# Upstream.net
KiCad netlist of a schematic drawn in Altium Designer
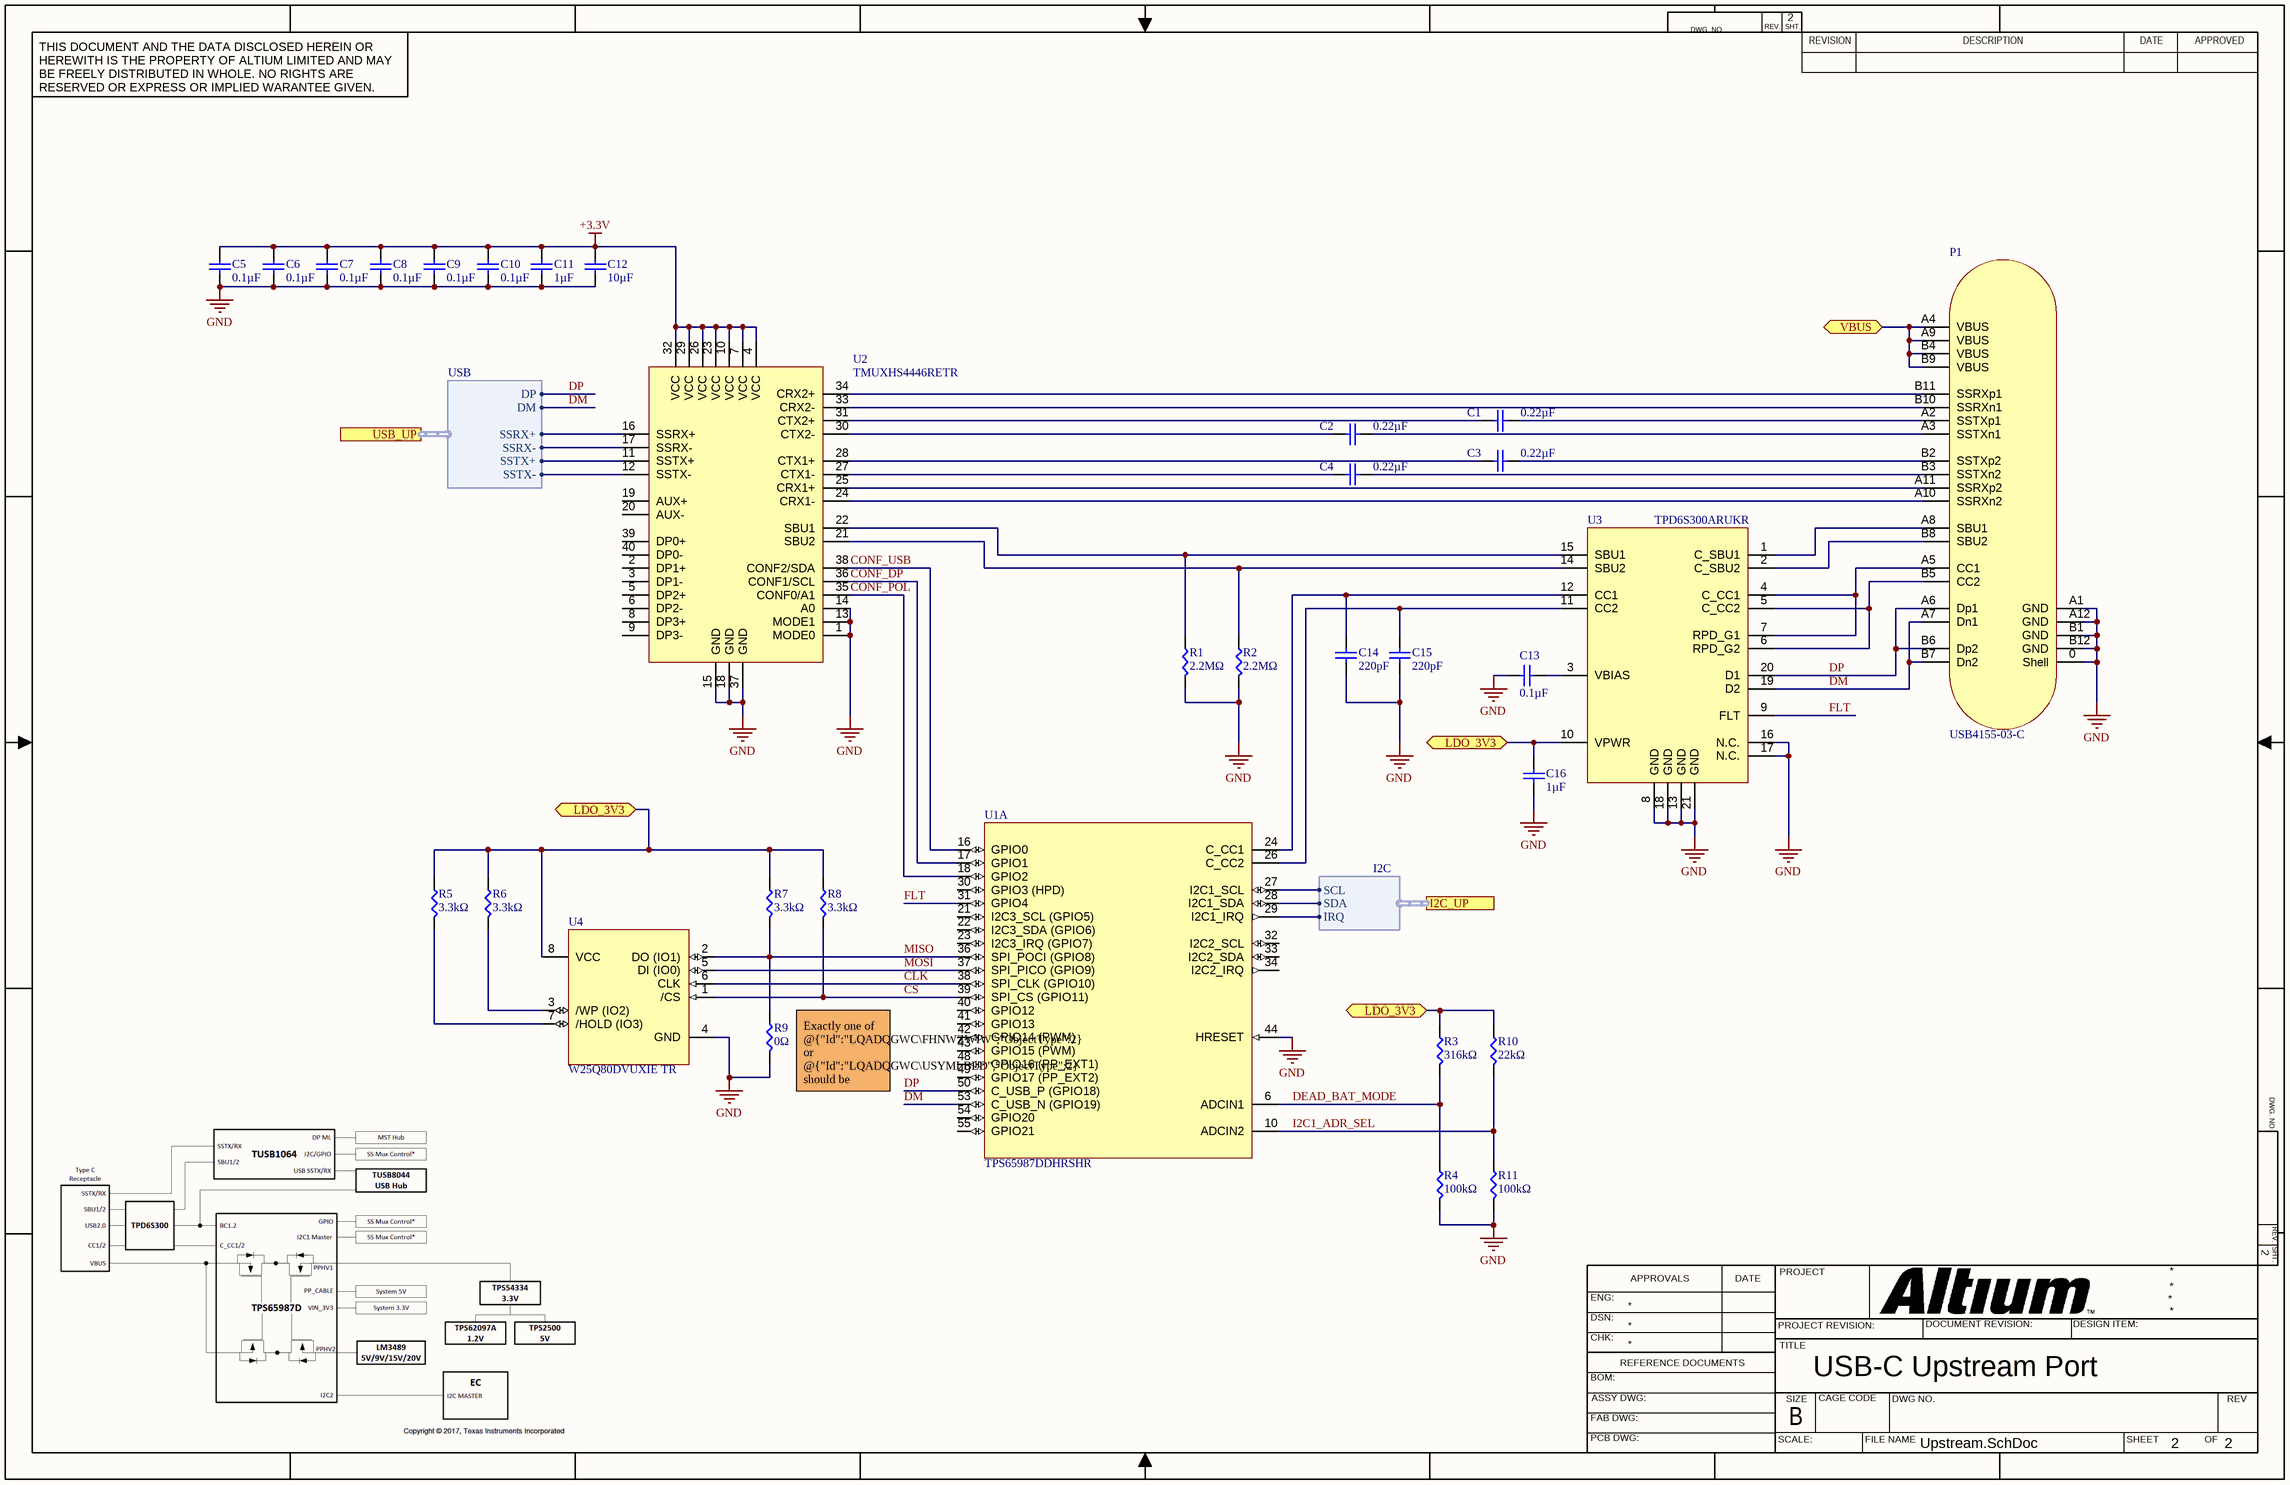
[diagram p0: Upstream.SchDoc]

(export (version "E")
  (design (tool "Eeschema 10.0.6"))
  (components
    (comp (ref "C1")
      (value "0.22µF")
      (footprint "CAP0402")
      (description "0.22 µF ±10% 50V Ceramic Capacitor X5R 0402 (1005 Metric)")
      (fields (field (name "VOLTAGE") "50V") (field (name "Comment") "UMK105BJ224KV-F"))
      (libsource (lib "Schlib1") (part "UMK105BJ224KV-F"))
    )
    (comp (ref "C2")
      (value "0.22µF")
      (footprint "CAP0402")
      (description "0.22 µF ±10% 50V Ceramic Capacitor X5R 0402 (1005 Metric)")
      (fields (field (name "VOLTAGE") "50V") (field (name "Comment") "UMK105BJ224KV-F"))
      (libsource (lib "Schlib1") (part "UMK105BJ224KV-F"))
    )
    (comp (ref "C3")
      (value "0.22µF")
      (footprint "CAP0402")
      (description "0.22 µF ±10% 50V Ceramic Capacitor X5R 0402 (1005 Metric)")
      (fields (field (name "VOLTAGE") "50V") (field (name "Comment") "UMK105BJ224KV-F"))
      (libsource (lib "Schlib1") (part "UMK105BJ224KV-F"))
    )
    (comp (ref "C4")
      (value "0.22µF")
      (footprint "CAP0402")
      (description "0.22 µF ±10% 50V Ceramic Capacitor X5R 0402 (1005 Metric)")
      (fields (field (name "VOLTAGE") "50V") (field (name "Comment") "UMK105BJ224KV-F"))
      (libsource (lib "Schlib1") (part "UMK105BJ224KV-F"))
    )
    (comp (ref "C5")
      (value "0.1µF")
      (footprint "CAP0402")
      (description "0.1 µF ±10% 50V Ceramic Capacitor X5R 0402 (1005 Metric)")
      (fields (field (name "VOLTAGE") "50V") (field (name "Comment") "CC0402KRX5R9BB104"))
      (libsource (lib "Schlib1") (part "CC0402KRX5R9BB104"))
    )
    (comp (ref "C6")
      (value "0.1µF")
      (footprint "CAP0402")
      (description "0.1 µF ±10% 50V Ceramic Capacitor X5R 0402 (1005 Metric)")
      (fields (field (name "VOLTAGE") "50V") (field (name "Comment") "CC0402KRX5R9BB104"))
      (libsource (lib "Schlib1") (part "CC0402KRX5R9BB104"))
    )
    (comp (ref "C7")
      (value "0.1µF")
      (footprint "CAP0402")
      (description "0.1 µF ±10% 50V Ceramic Capacitor X5R 0402 (1005 Metric)")
      (fields (field (name "VOLTAGE") "50V") (field (name "Comment") "CC0402KRX5R9BB104"))
      (libsource (lib "Schlib1") (part "CC0402KRX5R9BB104"))
    )
    (comp (ref "C8")
      (value "0.1µF")
      (footprint "CAP0402")
      (description "0.1 µF ±10% 50V Ceramic Capacitor X5R 0402 (1005 Metric)")
      (fields (field (name "VOLTAGE") "50V") (field (name "Comment") "CC0402KRX5R9BB104"))
      (libsource (lib "Schlib1") (part "CC0402KRX5R9BB104"))
    )
    (comp (ref "C9")
      (value "0.1µF")
      (footprint "CAP0402")
      (description "0.1 µF ±10% 50V Ceramic Capacitor X5R 0402 (1005 Metric)")
      (fields (field (name "VOLTAGE") "50V") (field (name "Comment") "CC0402KRX5R9BB104"))
      (libsource (lib "Schlib1") (part "CC0402KRX5R9BB104"))
    )
    (comp (ref "C10")
      (value "0.1µF")
      (footprint "CAP0402")
      (description "0.1 µF ±10% 50V Ceramic Capacitor X5R 0402 (1005 Metric)")
      (fields (field (name "VOLTAGE") "50V") (field (name "Comment") "CC0402KRX5R9BB104"))
      (libsource (lib "Schlib1") (part "CC0402KRX5R9BB104"))
    )
    (comp (ref "C11")
      (value "1µF")
      (footprint "CAP0402")
      (description "1 µF ±10% 16V Ceramic Capacitor X5R 0402 (1005 Metric)")
      (fields (field (name "VOLTAGE") "16V") (field (name "Comment") "CL05A105KO5NNNC"))
      (libsource (lib "Schlib1") (part "CL05A105KO5NNNC"))
    )
    (comp (ref "C12")
      (value "10µF")
      (footprint "CAP0402")
      (description "10 µF ±20% 6.3V Ceramic Capacitor X5R 0402 (1005 Metric)")
      (fields (field (name "VOLTAGE") "6.3V") (field (name "Comment") "CL05A106MQ5NUNC"))
      (libsource (lib "Schlib1") (part "CL05A106MQ5NUNC"))
    )
    (comp (ref "C13")
      (value "0.1µF")
      (footprint "CAP0402")
      (description "0.1 µF ±10% 50V Ceramic Capacitor X5R 0402 (1005 Metric)")
      (fields (field (name "VOLTAGE") "50V") (field (name "Comment") "CC0402KRX5R9BB104"))
      (libsource (lib "Schlib1") (part "CC0402KRX5R9BB104"))
    )
    (comp (ref "C14")
      (value "220pF")
      (footprint "CAP0402")
      (description "220 pF ±5% 50V Ceramic Capacitor C0G, NP0 0402 (1005 Metric)")
      (fields (field (name "VOLTAGE") "50V") (field (name "Comment") "GRM1555C1H221JA01D"))
      (libsource (lib "Schlib1") (part "GRM1555C1H221JA01D"))
    )
    (comp (ref "C15")
      (value "220pF")
      (footprint "CAP0402")
      (description "220 pF ±5% 50V Ceramic Capacitor C0G, NP0 0402 (1005 Metric)")
      (fields (field (name "VOLTAGE") "50V") (field (name "Comment") "GRM1555C1H221JA01D"))
      (libsource (lib "Schlib1") (part "GRM1555C1H221JA01D"))
    )
    (comp (ref "C16")
      (value "1µF")
      (footprint "CAP0402")
      (description "1 µF ±10% 16V Ceramic Capacitor X5R 0402 (1005 Metric)")
      (fields (field (name "VOLTAGE") "16V") (field (name "Comment") "CL05A105KO5NNNC"))
      (libsource (lib "Schlib1") (part "CL05A105KO5NNNC"))
    )
    (comp (ref "P1")
      (value "USB4155-03-C")
      (footprint "USB4155-03-C")
      (fields (field (name "MANUFACTURER") "GCT") (field (name "VOLTAGE") "48VDC"))
      (libsource (lib "Schlib1") (part "USB4155-03-C"))
    )
    (comp (ref "R1")
      (value "2.2MΩ")
      (footprint "RES0402")
      (description "2.2 MOhms ±1% 0.063W, 1/16W Chip Resistor 0402 (1005 Metric) Moisture Resistant Thick Film")
      (fields (field (name "Comment") "RC0402FR-072M2L"))
      (libsource (lib "Schlib1") (part "RC0402FR-072M2L"))
    )
    (comp (ref "R2")
      (value "2.2MΩ")
      (footprint "RES0402")
      (description "2.2 MOhms ±1% 0.063W, 1/16W Chip Resistor 0402 (1005 Metric) Moisture Resistant Thick Film")
      (fields (field (name "Comment") "RC0402FR-072M2L"))
      (libsource (lib "Schlib1") (part "RC0402FR-072M2L"))
    )
    (comp (ref "R3")
      (value "316kΩ")
      (footprint "RES0402")
      (description "316 kOhms ±1% 0.1W, 1/10W Chip Resistor 0402 (1005 Metric) Automotive AEC-Q200 Thick Film")
      (fields (field (name "Comment") "CRCW0402316KFKED"))
      (libsource (lib "Schlib1") (part "CRCW0402316KFKED"))
    )
    (comp (ref "R4")
      (value "100kΩ")
      (footprint "RES0402")
      (description "100 kOhms ±1% 0.1W, 1/10W Chip Resistor 0402 (1005 Metric) Automotive AEC-Q200 Thick Film")
      (fields (field (name "Comment") "ERJ-2RKF1003X"))
      (libsource (lib "Schlib1") (part "ERJ-2RKF1003X"))
    )
    (comp (ref "R5")
      (value "3.3kΩ")
      (footprint "RES0402")
      (description "3.3 kOhms ±0.1% 0.063W, 1/16W Chip Resistor 0402 (1005 Metric) Automotive AEC-Q200 Thin Film")
      (fields (field (name "Comment") "ERA-2AEB332X"))
      (libsource (lib "Schlib1") (part "ERA-2AEB332X"))
    )
    (comp (ref "R6")
      (value "3.3kΩ")
      (footprint "RES0402")
      (description "3.3 kOhms ±0.1% 0.063W, 1/16W Chip Resistor 0402 (1005 Metric) Automotive AEC-Q200 Thin Film")
      (fields (field (name "Comment") "ERA-2AEB332X"))
      (libsource (lib "Schlib1") (part "ERA-2AEB332X"))
    )
    (comp (ref "R7")
      (value "3.3kΩ")
      (footprint "RES0402")
      (description "3.3 kOhms ±0.1% 0.063W, 1/16W Chip Resistor 0402 (1005 Metric) Automotive AEC-Q200 Thin Film")
      (fields (field (name "Comment") "ERA-2AEB332X"))
      (libsource (lib "Schlib1") (part "ERA-2AEB332X"))
    )
    (comp (ref "R8")
      (value "3.3kΩ")
      (footprint "RES0402")
      (description "3.3 kOhms ±0.1% 0.063W, 1/16W Chip Resistor 0402 (1005 Metric) Automotive AEC-Q200 Thin Film")
      (fields (field (name "Comment") "ERA-2AEB332X"))
      (libsource (lib "Schlib1") (part "ERA-2AEB332X"))
    )
    (comp (ref "R9")
      (value "0Ω")
      (footprint "RES0402")
      (description "0 Ohms Jumper Chip Resistor 0402 (1005 Metric) Moisture Resistant Thick Film")
      (fields (field (name "Comment") "RC0402JR-070RL"))
      (libsource (lib "Schlib1") (part "RC0402JR-070RL"))
    )
    (comp (ref "R10")
      (value "22kΩ")
      (footprint "RES0402")
      (description "22 kOhms ±1% 0.1W, 1/10W Chip Resistor 0402 (1005 Metric) Automotive AEC-Q200 Thick Film")
      (fields (field (name "Comment") "ERJ-2RKF2202X"))
      (libsource (lib "Schlib1") (part "ERJ-2RKF2202X"))
    )
    (comp (ref "R11")
      (value "100kΩ")
      (footprint "RES0402")
      (description "100 kOhms ±1% 0.1W, 1/10W Chip Resistor 0402 (1005 Metric) Automotive AEC-Q200 Thick Film")
      (fields (field (name "Comment") "ERJ-2RKF1003X"))
      (libsource (lib "Schlib1") (part "ERJ-2RKF1003X"))
    )
    (comp (ref "U1")
      (value "TPS65987DDHRSHR")
      (footprint "56-VQFN (7x7)")
      (description "USB, Type-C Controller PMIC 56-VQFN (7x7)")
      (fields (field (name "MANUFACTURER") "Texas Instruments"))
      (libsource (lib "Schlib1") (part "TPS65987DDHRSHR"))
    )
    (comp (ref "U2")
      (value "TMUXHS4446RETR")
      (description "4 Circuit IC Switch 4:4 7Ohm (Typ) 40-WQFN (6x3)")
      (fields (field (name "MANUFACTURER") "Texas Instruments"))
      (libsource (lib "Schlib1") (part "TMUXHS4446RETR"))
    )
    (comp (ref "U3")
      (value "TPD6S300ARUKR")
      (description "Overvoltage/Surge Protection IC 8V Internal Switch 20-WQFN (3x3)")
      (fields (field (name "MANUFACTURER") "Texas Instruments"))
      (libsource (lib "Schlib1") (part "TPD6S300ARUKR"))
    )
    (comp (ref "U4")
      (value "W25Q80DVUXIE TR")
      (description "FLASH - NOR Memory IC 8Mbit SPI - Quad I/O 104 MHz 8-USON (2x3)")
      (fields (field (name "MANUFACTURER") "Winbond Electronics"))
      (libsource (lib "Schlib1") (part "W25Q80DVUXIE TR"))
    )
  )
  (nets
    (net (code "3") (name "+3.3V") (class "Default")
      (node (ref "C10") (pin "2") (pinfunction "2_2") (pintype "passive"))
      (node (ref "C11") (pin "2") (pinfunction "2_2") (pintype "passive"))
      (node (ref "C12") (pin "2") (pinfunction "2_2") (pintype "passive"))
      (node (ref "C5") (pin "2") (pinfunction "2_2") (pintype "passive"))
      (node (ref "C6") (pin "2") (pinfunction "2_2") (pintype "passive"))
      (node (ref "C7") (pin "2") (pinfunction "2_2") (pintype "passive"))
      (node (ref "C8") (pin "2") (pinfunction "2_2") (pintype "passive"))
      (node (ref "C9") (pin "2") (pinfunction "2_2") (pintype "passive"))
      (node (ref "U2") (pin "10") (pinfunction "VCC_10") (pintype "passive"))
      (node (ref "U2") (pin "23") (pinfunction "VCC_23") (pintype "passive"))
      (node (ref "U2") (pin "26") (pinfunction "VCC_26") (pintype "passive"))
      (node (ref "U2") (pin "29") (pinfunction "VCC_29") (pintype "passive"))
      (node (ref "U2") (pin "32") (pinfunction "VCC_32") (pintype "passive"))
      (node (ref "U2") (pin "4") (pinfunction "VCC_4") (pintype "passive"))
      (node (ref "U2") (pin "7") (pinfunction "VCC_7") (pintype "passive"))
    )
    (net (code "4") (name "/CLK") (class "Default")
      (node (ref "U1") (pin "38") (pinfunction "SPI_CLK_(GPIO10)_38") (pintype "bidirectional"))
      (node (ref "U4") (pin "6") (pinfunction "CLK_6") (pintype "input"))
    )
    (net (code "5") (name "/CONF_DP") (class "Default")
      (node (ref "U1") (pin "17") (pinfunction "GPIO1_17") (pintype "bidirectional"))
      (node (ref "U2") (pin "36") (pinfunction "CONF1/SCL_36") (pintype "passive"))
    )
    (net (code "6") (name "/CONF_POL") (class "Default")
      (node (ref "U1") (pin "18") (pinfunction "GPIO2_18") (pintype "bidirectional"))
      (node (ref "U2") (pin "35") (pinfunction "CONF0/A1_35") (pintype "passive"))
    )
    (net (code "7") (name "/CONF_USB") (class "Default")
      (node (ref "U1") (pin "16") (pinfunction "GPIO0_16") (pintype "bidirectional"))
      (node (ref "U2") (pin "38") (pinfunction "CONF2/SDA_38") (pintype "passive"))
    )
    (net (code "8") (name "/CS") (class "Default")
      (node (ref "R8") (pin "1") (pinfunction "1_1") (pintype "passive"))
      (node (ref "U1") (pin "39") (pinfunction "SPI_CS_(GPIO11)_39") (pintype "bidirectional"))
      (node (ref "U4") (pin "1") (pinfunction "/CS_1") (pintype "input"))
    )
    (net (code "9") (name "/DEAD_BAT_MODE") (class "Default")
      (node (ref "R3") (pin "1") (pinfunction "1_1") (pintype "passive"))
      (node (ref "R4") (pin "2") (pinfunction "2_2") (pintype "passive"))
      (node (ref "U1") (pin "6") (pinfunction "ADCIN1_6") (pintype "passive"))
    )
    (net (code "10") (name "/DM") (class "Default")
      (node (ref "P1") (pin "A7") (pinfunction "Dn1_A7") (pintype "passive"))
      (node (ref "P1") (pin "B7") (pinfunction "Dn2_B7") (pintype "passive"))
      (node (ref "U1") (pin "53") (pinfunction "C_USB_N_(GPIO19)_53") (pintype "bidirectional"))
      (node (ref "U3") (pin "19") (pinfunction "D2_19") (pintype "passive"))
    )
    (net (code "11") (name "/DP") (class "Default")
      (node (ref "P1") (pin "A6") (pinfunction "Dp1_A6") (pintype "passive"))
      (node (ref "P1") (pin "B6") (pinfunction "Dp2_B6") (pintype "passive"))
      (node (ref "U1") (pin "50") (pinfunction "C_USB_P_(GPIO18)_50") (pintype "bidirectional"))
      (node (ref "U3") (pin "20") (pinfunction "D1_20") (pintype "passive"))
    )
    (net (code "12") (name "/FLT") (class "Default")
      (node (ref "U1") (pin "31") (pinfunction "GPIO4_31") (pintype "bidirectional"))
      (node (ref "U3") (pin "9") (pinfunction "FLT_9") (pintype "passive"))
    )
    (net (code "13") (name "/I2C1_ADR_SEL") (class "Default")
      (node (ref "R10") (pin "1") (pinfunction "1_1") (pintype "passive"))
      (node (ref "R11") (pin "2") (pinfunction "2_2") (pintype "passive"))
      (node (ref "U1") (pin "10") (pinfunction "ADCIN2_10") (pintype "passive"))
    )
    (net (code "14") (name "/IRQ") (class "Default")
      (node (ref "U1") (pin "29") (pinfunction "I2C1_IRQ_29") (pintype "output"))
    )
    (net (code "15") (name "/LDO_3V3") (class "Default")
      (node (ref "C16") (pin "2") (pinfunction "2_2") (pintype "passive"))
      (node (ref "R10") (pin "2") (pinfunction "2_2") (pintype "passive"))
      (node (ref "R3") (pin "2") (pinfunction "2_2") (pintype "passive"))
      (node (ref "R5") (pin "2") (pinfunction "2_2") (pintype "passive"))
      (node (ref "R6") (pin "2") (pinfunction "2_2") (pintype "passive"))
      (node (ref "R7") (pin "2") (pinfunction "2_2") (pintype "passive"))
      (node (ref "R8") (pin "2") (pinfunction "2_2") (pintype "passive"))
      (node (ref "U3") (pin "10") (pinfunction "VPWR_10") (pintype "passive"))
      (node (ref "U4") (pin "8") (pinfunction "VCC_8") (pintype "passive"))
    )
    (net (code "16") (name "/MISO") (class "Default")
      (node (ref "R7") (pin "1") (pinfunction "1_1") (pintype "passive"))
      (node (ref "R9") (pin "2") (pinfunction "2_2") (pintype "passive"))
      (node (ref "U1") (pin "36") (pinfunction "SPI_POCI_(GPIO8)_36") (pintype "bidirectional"))
      (node (ref "U4") (pin "2") (pinfunction "DO_(IO1)_2") (pintype "bidirectional"))
    )
    (net (code "17") (name "/MOSI") (class "Default")
      (node (ref "U1") (pin "37") (pinfunction "SPI_PICO_(GPIO9)_37") (pintype "bidirectional"))
      (node (ref "U4") (pin "5") (pinfunction "DI_(IO0)_5") (pintype "bidirectional"))
    )
    (net (code "18") (name "/SCL") (class "Default")
      (node (ref "U1") (pin "27") (pinfunction "I2C1_SCL_27") (pintype "bidirectional"))
    )
    (net (code "19") (name "/SDA") (class "Default")
      (node (ref "U1") (pin "28") (pinfunction "I2C1_SDA_28") (pintype "bidirectional"))
    )
    (net (code "20") (name "/SSRX+") (class "Default")
      (node (ref "U2") (pin "16") (pinfunction "SSRX+_16") (pintype "passive"))
    )
    (net (code "21") (name "/SSRX-") (class "Default")
      (node (ref "U2") (pin "17") (pinfunction "SSRX-_17") (pintype "passive"))
    )
    (net (code "22") (name "/SSTX+") (class "Default")
      (node (ref "U2") (pin "11") (pinfunction "SSTX+_11") (pintype "passive"))
    )
    (net (code "23") (name "/SSTX-") (class "Default")
      (node (ref "U2") (pin "12") (pinfunction "SSTX-_12") (pintype "passive"))
    )
    (net (code "24") (name "/VBUS") (class "Default")
      (node (ref "P1") (pin "A4") (pinfunction "VBUS_A4") (pintype "passive"))
      (node (ref "P1") (pin "A9") (pinfunction "VBUS_A9") (pintype "passive"))
      (node (ref "P1") (pin "B4") (pinfunction "VBUS_B4") (pintype "passive"))
      (node (ref "P1") (pin "B9") (pinfunction "VBUS_B9") (pintype "passive"))
    )
    (net (code "27") (name "GND") (class "Default")
      (node (ref "C10") (pin "1") (pinfunction "1_1") (pintype "passive"))
      (node (ref "C11") (pin "1") (pinfunction "1_1") (pintype "passive"))
      (node (ref "C12") (pin "1") (pinfunction "1_1") (pintype "passive"))
      (node (ref "C13") (pin "1") (pinfunction "1_1") (pintype "passive"))
      (node (ref "C14") (pin "1") (pinfunction "1_1") (pintype "passive"))
      (node (ref "C15") (pin "1") (pinfunction "1_1") (pintype "passive"))
      (node (ref "C16") (pin "1") (pinfunction "1_1") (pintype "passive"))
      (node (ref "C5") (pin "1") (pinfunction "1_1") (pintype "passive"))
      (node (ref "C6") (pin "1") (pinfunction "1_1") (pintype "passive"))
      (node (ref "C7") (pin "1") (pinfunction "1_1") (pintype "passive"))
      (node (ref "C8") (pin "1") (pinfunction "1_1") (pintype "passive"))
      (node (ref "C9") (pin "1") (pinfunction "1_1") (pintype "passive"))
      (node (ref "P1") (pin "0") (pinfunction "Shell_0") (pintype "passive"))
      (node (ref "P1") (pin "A1") (pinfunction "GND_A1") (pintype "passive"))
      (node (ref "P1") (pin "A12") (pinfunction "GND_A12") (pintype "passive"))
      (node (ref "P1") (pin "B1") (pinfunction "GND_B1") (pintype "passive"))
      (node (ref "P1") (pin "B12") (pinfunction "GND_B12") (pintype "passive"))
      (node (ref "R1") (pin "1") (pinfunction "1_1") (pintype "passive"))
      (node (ref "R11") (pin "1") (pinfunction "1_1") (pintype "passive"))
      (node (ref "R2") (pin "1") (pinfunction "1_1") (pintype "passive"))
      (node (ref "R4") (pin "1") (pinfunction "1_1") (pintype "passive"))
      (node (ref "R9") (pin "1") (pinfunction "1_1") (pintype "passive"))
      (node (ref "U1") (pin "44") (pinfunction "HRESET_44") (pintype "input"))
      (node (ref "U2") (pin "1") (pinfunction "MODE0_1") (pintype "passive"))
      (node (ref "U2") (pin "13") (pinfunction "MODE1_13") (pintype "passive"))
      (node (ref "U2") (pin "14") (pinfunction "A0_14") (pintype "passive"))
      (node (ref "U2") (pin "15") (pinfunction "GND_15") (pintype "passive"))
      (node (ref "U2") (pin "18") (pinfunction "GND_18") (pintype "passive"))
      (node (ref "U2") (pin "37") (pinfunction "GND_37") (pintype "passive"))
      (node (ref "U3") (pin "13") (pinfunction "GND_13") (pintype "passive"))
      (node (ref "U3") (pin "16") (pinfunction "N.C._16") (pintype "passive"))
      (node (ref "U3") (pin "17") (pinfunction "N.C._17") (pintype "passive"))
      (node (ref "U3") (pin "18") (pinfunction "GND_18") (pintype "passive"))
      (node (ref "U3") (pin "21") (pinfunction "GND_21") (pintype "passive"))
      (node (ref "U3") (pin "8") (pinfunction "GND_8") (pintype "passive"))
      (node (ref "U4") (pin "4") (pinfunction "GND_4") (pintype "passive"))
    )
    (net (code "28") (name "Net-(P1-CC1)") (class "Default")
      (node (ref "P1") (pin "A5") (pinfunction "CC1_A5") (pintype "passive"))
      (node (ref "U3") (pin "4") (pinfunction "C_CC1_4") (pintype "passive"))
      (node (ref "U3") (pin "7") (pinfunction "RPD_G1_7") (pintype "passive"))
    )
    (net (code "29") (name "Net-(P1-CC2)") (class "Default")
      (node (ref "P1") (pin "B5") (pinfunction "CC2_B5") (pintype "passive"))
      (node (ref "U3") (pin "5") (pinfunction "C_CC2_5") (pintype "passive"))
      (node (ref "U3") (pin "6") (pinfunction "RPD_G2_6") (pintype "passive"))
    )
    (net (code "30") (name "Net-(P1-SBU1)") (class "Default")
      (node (ref "P1") (pin "A8") (pinfunction "SBU1_A8") (pintype "passive"))
      (node (ref "U3") (pin "1") (pinfunction "C_SBU1_1") (pintype "passive"))
    )
    (net (code "31") (name "Net-(P1-SBU2)") (class "Default")
      (node (ref "P1") (pin "B8") (pinfunction "SBU2_B8") (pintype "passive"))
      (node (ref "U3") (pin "2") (pinfunction "C_SBU2_2") (pintype "passive"))
    )
    (net (code "32") (name "Net-(P1-SSRXn1)") (class "Default")
      (node (ref "P1") (pin "B10") (pinfunction "SSRXn1_B10") (pintype "passive"))
      (node (ref "U2") (pin "33") (pinfunction "CRX2-_33") (pintype "passive"))
    )
    (net (code "33") (name "Net-(P1-SSRXn2)") (class "Default")
      (node (ref "P1") (pin "A10") (pinfunction "SSRXn2_A10") (pintype "passive"))
      (node (ref "U2") (pin "24") (pinfunction "CRX1-_24") (pintype "passive"))
    )
    (net (code "34") (name "Net-(P1-SSRXp1)") (class "Default")
      (node (ref "P1") (pin "B11") (pinfunction "SSRXp1_B11") (pintype "passive"))
      (node (ref "U2") (pin "34") (pinfunction "CRX2+_34") (pintype "passive"))
    )
    (net (code "35") (name "Net-(P1-SSRXp2)") (class "Default")
      (node (ref "P1") (pin "A11") (pinfunction "SSRXp2_A11") (pintype "passive"))
      (node (ref "U2") (pin "25") (pinfunction "CRX1+_25") (pintype "passive"))
    )
    (net (code "36") (name "Net-(P1-SSTXn1)") (class "Default")
      (node (ref "C2") (pin "2") (pinfunction "2_2") (pintype "passive"))
      (node (ref "P1") (pin "A3") (pinfunction "SSTXn1_A3") (pintype "passive"))
    )
    (net (code "37") (name "Net-(P1-SSTXn2)") (class "Default")
      (node (ref "C4") (pin "2") (pinfunction "2_2") (pintype "passive"))
      (node (ref "P1") (pin "B3") (pinfunction "SSTXn2_B3") (pintype "passive"))
    )
    (net (code "38") (name "Net-(P1-SSTXp1)") (class "Default")
      (node (ref "C1") (pin "2") (pinfunction "2_2") (pintype "passive"))
      (node (ref "P1") (pin "A2") (pinfunction "SSTXp1_A2") (pintype "passive"))
    )
    (net (code "39") (name "Net-(P1-SSTXp2)") (class "Default")
      (node (ref "C3") (pin "2") (pinfunction "2_2") (pintype "passive"))
      (node (ref "P1") (pin "B2") (pinfunction "SSTXp2_B2") (pintype "passive"))
    )
    (net (code "40") (name "Net-(U1A-C_CC1)") (class "Default")
      (node (ref "C14") (pin "2") (pinfunction "2_2") (pintype "passive"))
      (node (ref "U1") (pin "24") (pinfunction "C_CC1_24") (pintype "passive"))
      (node (ref "U3") (pin "12") (pinfunction "CC1_12") (pintype "passive"))
    )
    (net (code "41") (name "Net-(U1A-C_CC2)") (class "Default")
      (node (ref "C15") (pin "2") (pinfunction "2_2") (pintype "passive"))
      (node (ref "U1") (pin "26") (pinfunction "C_CC2_26") (pintype "passive"))
      (node (ref "U3") (pin "11") (pinfunction "CC2_11") (pintype "passive"))
    )
    (net (code "42") (name "Net-(U2-CTX1+)") (class "Default")
      (node (ref "C3") (pin "1") (pinfunction "1_1") (pintype "passive"))
      (node (ref "U2") (pin "28") (pinfunction "CTX1+_28") (pintype "passive"))
    )
    (net (code "43") (name "Net-(U2-CTX1-)") (class "Default")
      (node (ref "C4") (pin "1") (pinfunction "1_1") (pintype "passive"))
      (node (ref "U2") (pin "27") (pinfunction "CTX1-_27") (pintype "passive"))
    )
    (net (code "44") (name "Net-(U2-CTX2+)") (class "Default")
      (node (ref "C1") (pin "1") (pinfunction "1_1") (pintype "passive"))
      (node (ref "U2") (pin "31") (pinfunction "CTX2+_31") (pintype "passive"))
    )
    (net (code "45") (name "Net-(U2-CTX2-)") (class "Default")
      (node (ref "C2") (pin "1") (pinfunction "1_1") (pintype "passive"))
      (node (ref "U2") (pin "30") (pinfunction "CTX2-_30") (pintype "passive"))
    )
    (net (code "46") (name "Net-(U2-SBU1)") (class "Default")
      (node (ref "R1") (pin "2") (pinfunction "2_2") (pintype "passive"))
      (node (ref "U2") (pin "22") (pinfunction "SBU1_22") (pintype "passive"))
      (node (ref "U3") (pin "15") (pinfunction "SBU1_15") (pintype "passive"))
    )
    (net (code "47") (name "Net-(U2-SBU2)") (class "Default")
      (node (ref "R2") (pin "2") (pinfunction "2_2") (pintype "passive"))
      (node (ref "U2") (pin "21") (pinfunction "SBU2_21") (pintype "passive"))
      (node (ref "U3") (pin "14") (pinfunction "SBU2_14") (pintype "passive"))
    )
    (net (code "48") (name "Net-(U3-VBIAS)") (class "Default")
      (node (ref "C13") (pin "2") (pinfunction "2_2") (pintype "passive"))
      (node (ref "U3") (pin "3") (pinfunction "VBIAS_3") (pintype "passive"))
    )
    (net (code "49") (name "Net-(U4-{slash}HOLD_(IO3))") (class "Default")
      (node (ref "R5") (pin "1") (pinfunction "1_1") (pintype "passive"))
      (node (ref "U4") (pin "7") (pinfunction "/HOLD_(IO3)_7") (pintype "bidirectional"))
    )
    (net (code "50") (name "Net-(U4-{slash}WP_(IO2))") (class "Default")
      (node (ref "R6") (pin "1") (pinfunction "1_1") (pintype "passive"))
      (node (ref "U4") (pin "3") (pinfunction "/WP_(IO2)_3") (pintype "bidirectional"))
    )
    (net (code "51") (name "unconnected-(U1A-GPIO3_(HPD)-Pad30)") (class "Default")
      (node (ref "U1") (pin "30") (pinfunction "GPIO3_(HPD)_30") (pintype "bidirectional"))
    )
    (net (code "52") (name "unconnected-(U1A-GPIO12-Pad40)") (class "Default")
      (node (ref "U1") (pin "40") (pinfunction "GPIO12_40") (pintype "bidirectional"))
    )
    (net (code "53") (name "unconnected-(U1A-GPIO13-Pad41)") (class "Default")
      (node (ref "U1") (pin "41") (pinfunction "GPIO13_41") (pintype "bidirectional"))
    )
    (net (code "54") (name "unconnected-(U1A-GPIO14_(PWM)-Pad42)") (class "Default")
      (node (ref "U1") (pin "42") (pinfunction "GPIO14_(PWM)_42") (pintype "bidirectional"))
    )
    (net (code "55") (name "unconnected-(U1A-GPIO15_(PWM)-Pad43)") (class "Default")
      (node (ref "U1") (pin "43") (pinfunction "GPIO15_(PWM)_43") (pintype "bidirectional"))
    )
    (net (code "56") (name "unconnected-(U1A-GPIO16_(PP_EXT1)-Pad48)") (class "Default")
      (node (ref "U1") (pin "48") (pinfunction "GPIO16_(PP_EXT1)_48") (pintype "bidirectional"))
    )
    (net (code "57") (name "unconnected-(U1A-GPIO17_(PP_EXT2)-Pad49)") (class "Default")
      (node (ref "U1") (pin "49") (pinfunction "GPIO17_(PP_EXT2)_49") (pintype "bidirectional"))
    )
    (net (code "58") (name "unconnected-(U1A-GPIO20-Pad54)") (class "Default")
      (node (ref "U1") (pin "54") (pinfunction "GPIO20_54") (pintype "bidirectional"))
    )
    (net (code "59") (name "unconnected-(U1A-GPIO21-Pad55)") (class "Default")
      (node (ref "U1") (pin "55") (pinfunction "GPIO21_55") (pintype "bidirectional"))
    )
    (net (code "60") (name "unconnected-(U1A-I2C2_IRQ-Pad34)") (class "Default")
      (node (ref "U1") (pin "34") (pinfunction "I2C2_IRQ_34") (pintype "output"))
    )
    (net (code "61") (name "unconnected-(U1A-I2C2_SCL-Pad32)") (class "Default")
      (node (ref "U1") (pin "32") (pinfunction "I2C2_SCL_32") (pintype "bidirectional"))
    )
    (net (code "62") (name "unconnected-(U1A-I2C2_SDA-Pad33)") (class "Default")
      (node (ref "U1") (pin "33") (pinfunction "I2C2_SDA_33") (pintype "bidirectional"))
    )
    (net (code "63") (name "unconnected-(U1A-I2C3_IRQ_(GPIO7)-Pad23)") (class "Default")
      (node (ref "U1") (pin "23") (pinfunction "I2C3_IRQ_(GPIO7)_23") (pintype "bidirectional"))
    )
    (net (code "64") (name "unconnected-(U1A-I2C3_SCL_(GPIO5)-Pad21)") (class "Default")
      (node (ref "U1") (pin "21") (pinfunction "I2C3_SCL_(GPIO5)_21") (pintype "bidirectional"))
    )
    (net (code "65") (name "unconnected-(U1A-I2C3_SDA_(GPIO6)-Pad22)") (class "Default")
      (node (ref "U1") (pin "22") (pinfunction "I2C3_SDA_(GPIO6)_22") (pintype "bidirectional"))
    )
    (net (code "66") (name "unconnected-(U2-AUX+-Pad19)") (class "Default")
      (node (ref "U2") (pin "19") (pinfunction "AUX+_19") (pintype "passive"))
    )
    (net (code "67") (name "unconnected-(U2-AUX--Pad20)") (class "Default")
      (node (ref "U2") (pin "20") (pinfunction "AUX-_20") (pintype "passive"))
    )
    (net (code "68") (name "unconnected-(U2-DP0+-Pad39)") (class "Default")
      (node (ref "U2") (pin "39") (pinfunction "DP0+_39") (pintype "passive"))
    )
    (net (code "69") (name "unconnected-(U2-DP0--Pad40)") (class "Default")
      (node (ref "U2") (pin "40") (pinfunction "DP0-_40") (pintype "passive"))
    )
    (net (code "70") (name "unconnected-(U2-DP1+-Pad2)") (class "Default")
      (node (ref "U2") (pin "2") (pinfunction "DP1+_2") (pintype "passive"))
    )
    (net (code "71") (name "unconnected-(U2-DP1--Pad3)") (class "Default")
      (node (ref "U2") (pin "3") (pinfunction "DP1-_3") (pintype "passive"))
    )
    (net (code "72") (name "unconnected-(U2-DP2+-Pad5)") (class "Default")
      (node (ref "U2") (pin "5") (pinfunction "DP2+_5") (pintype "passive"))
    )
    (net (code "73") (name "unconnected-(U2-DP2--Pad6)") (class "Default")
      (node (ref "U2") (pin "6") (pinfunction "DP2-_6") (pintype "passive"))
    )
    (net (code "74") (name "unconnected-(U2-DP3+-Pad8)") (class "Default")
      (node (ref "U2") (pin "8") (pinfunction "DP3+_8") (pintype "passive"))
    )
    (net (code "75") (name "unconnected-(U2-DP3--Pad9)") (class "Default")
      (node (ref "U2") (pin "9") (pinfunction "DP3-_9") (pintype "passive"))
    )
  )
)
